# BH1730FVC_sensor.net
KiCad netlist of a schematic drawn in Altium Designer
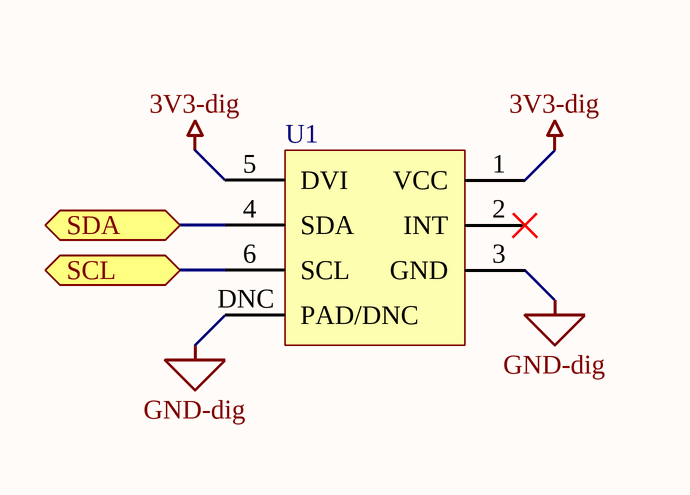
[diagram p0: BH1730FVC_sensor.SchDoc]

(export (version "E")
  (design (tool "Eeschema 10.0.6"))
  (components
    (comp (ref "U1")
      (value "BH1730FVC")
      (footprint "WSOF6")
      (description "Digital 16bit Serial Output Type  Ambient Light Sensor IC")
      (fields (field (name "MANUFACTURER") "ROHM") (field (name "MANUFACTURERPARTNUMBER") "BH1730FVC"))
      (libsource (lib "microcircuits") (part "BH1730FVC"))
    )
  )
  (nets
    (net (code "1") (name "/SCL") (class "Default")
      (node (ref "U1") (pin "6") (pinfunction "SCL_6") (pintype "open_collector"))
    )
    (net (code "2") (name "/SDA") (class "Default")
      (node (ref "U1") (pin "4") (pinfunction "SDA_4") (pintype "open_collector"))
    )
    (net (code "3") (name "3V3-dig") (class "Default")
      (node (ref "U1") (pin "1") (pinfunction "VCC_1") (pintype "power_in"))
      (node (ref "U1") (pin "5") (pinfunction "DVI_5") (pintype "passive"))
    )
    (net (code "4") (name "GND-dig") (class "Default")
      (node (ref "U1") (pin "3") (pinfunction "GND_3") (pintype "power_in"))
      (node (ref "U1") (pin "DNC") (pinfunction "PAD/DNC_DNC") (pintype "passive"))
    )
    (net (code "5") (name "unconnected-(U1-INT-Pad2)") (class "Default")
      (node (ref "U1") (pin "2") (pinfunction "INT_2") (pintype "open_collector+no_connect"))
    )
  )
)
